# Lia_Sonic.net
KiCad netlist of a schematic drawn in EAGLE
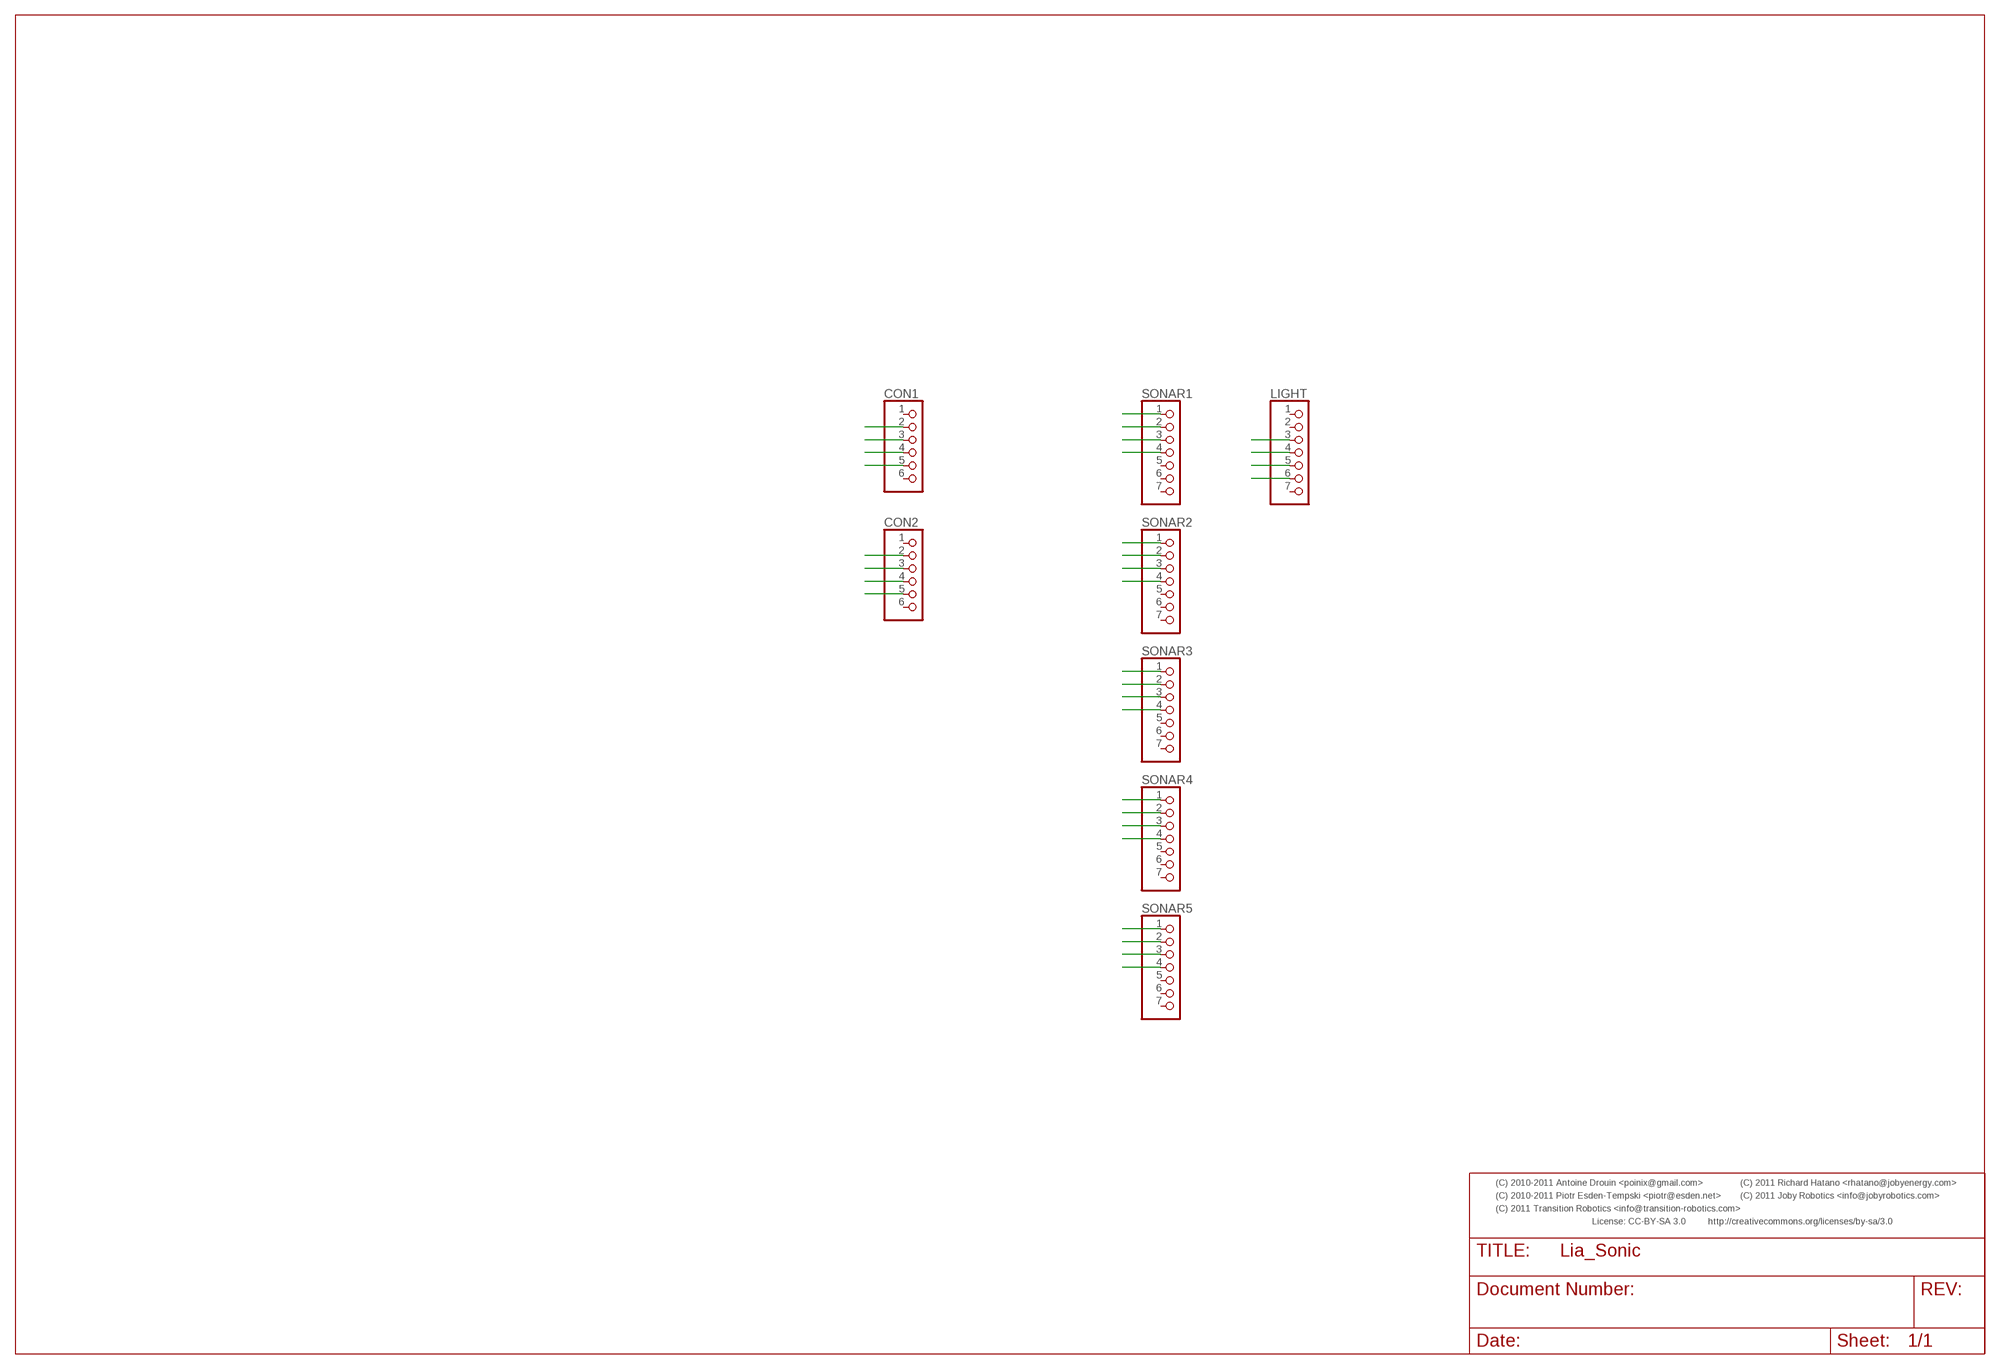
[diagram p0: schematic, sheet 1]

(export (version "E")
  (design (tool "Eeschema 10.0.6"))
  (components
    (comp (ref "CON1")
      (value "PINHD-1X6")
      (footprint "eagle-import:1X06")
      (libsource (lib "eagle-import") (part "PINHD-1X6"))
    )
    (comp (ref "CON2")
      (value "PINHD-1X6")
      (footprint "eagle-import:1X06")
      (libsource (lib "eagle-import") (part "PINHD-1X6"))
    )
    (comp (ref "LIGHT")
      (value "PINHD-1X7")
      (footprint "eagle-import:1X07")
      (libsource (lib "eagle-import") (part "PINHD-1X7"))
    )
    (comp (ref "SONAR1")
      (value "PINHD-1X7")
      (footprint "eagle-import:1X07")
      (libsource (lib "eagle-import") (part "PINHD-1X7"))
    )
    (comp (ref "SONAR2")
      (value "PINHD-1X7")
      (footprint "eagle-import:1X07")
      (libsource (lib "eagle-import") (part "PINHD-1X7"))
    )
    (comp (ref "SONAR3")
      (value "PINHD-1X7")
      (footprint "eagle-import:1X07")
      (libsource (lib "eagle-import") (part "PINHD-1X7"))
    )
    (comp (ref "SONAR4")
      (value "PINHD-1X7")
      (footprint "eagle-import:1X07")
      (libsource (lib "eagle-import") (part "PINHD-1X7"))
    )
    (comp (ref "SONAR5")
      (value "PINHD-1X7")
      (footprint "eagle-import:1X07")
      (libsource (lib "eagle-import") (part "PINHD-1X7"))
    )
  )
  (nets
    (net (code "1") (name "/GND") (class "Default")
      (node (ref "CON1") (pin "2") (pinfunction "2_2") (pintype "passive"))
      (node (ref "CON2") (pin "5") (pinfunction "5_5") (pintype "passive"))
      (node (ref "LIGHT") (pin "6") (pinfunction "6_6") (pintype "passive"))
      (node (ref "SONAR1") (pin "1") (pinfunction "1_1") (pintype "passive"))
      (node (ref "SONAR2") (pin "1") (pinfunction "1_1") (pintype "passive"))
      (node (ref "SONAR3") (pin "1") (pinfunction "1_1") (pintype "passive"))
      (node (ref "SONAR4") (pin "1") (pinfunction "1_1") (pintype "passive"))
      (node (ref "SONAR5") (pin "1") (pinfunction "1_1") (pintype "passive"))
    )
    (net (code "2") (name "/SCL") (class "Default")
      (node (ref "CON1") (pin "4") (pinfunction "4_4") (pintype "passive"))
      (node (ref "CON2") (pin "3") (pinfunction "3_3") (pintype "passive"))
      (node (ref "LIGHT") (pin "4") (pinfunction "4_4") (pintype "passive"))
      (node (ref "SONAR1") (pin "3") (pinfunction "3_3") (pintype "passive"))
      (node (ref "SONAR2") (pin "3") (pinfunction "3_3") (pintype "passive"))
      (node (ref "SONAR3") (pin "3") (pinfunction "3_3") (pintype "passive"))
      (node (ref "SONAR4") (pin "3") (pinfunction "3_3") (pintype "passive"))
      (node (ref "SONAR5") (pin "3") (pinfunction "3_3") (pintype "passive"))
    )
    (net (code "3") (name "/SDA") (class "Default")
      (node (ref "CON1") (pin "5") (pinfunction "5_5") (pintype "passive"))
      (node (ref "CON2") (pin "2") (pinfunction "2_2") (pintype "passive"))
      (node (ref "LIGHT") (pin "3") (pinfunction "3_3") (pintype "passive"))
      (node (ref "SONAR1") (pin "4") (pinfunction "4_4") (pintype "passive"))
      (node (ref "SONAR2") (pin "4") (pinfunction "4_4") (pintype "passive"))
      (node (ref "SONAR3") (pin "4") (pinfunction "4_4") (pintype "passive"))
      (node (ref "SONAR4") (pin "4") (pinfunction "4_4") (pintype "passive"))
      (node (ref "SONAR5") (pin "4") (pinfunction "4_4") (pintype "passive"))
    )
    (net (code "4") (name "/VCC") (class "Default")
      (node (ref "CON1") (pin "3") (pinfunction "3_3") (pintype "passive"))
      (node (ref "CON2") (pin "4") (pinfunction "4_4") (pintype "passive"))
      (node (ref "LIGHT") (pin "5") (pinfunction "5_5") (pintype "passive"))
      (node (ref "SONAR1") (pin "2") (pinfunction "2_2") (pintype "passive"))
      (node (ref "SONAR2") (pin "2") (pinfunction "2_2") (pintype "passive"))
      (node (ref "SONAR3") (pin "2") (pinfunction "2_2") (pintype "passive"))
      (node (ref "SONAR4") (pin "2") (pinfunction "2_2") (pintype "passive"))
      (node (ref "SONAR5") (pin "2") (pinfunction "2_2") (pintype "passive"))
    )
    (net (code "5") (name "unconnected-(CON1-Pad1)") (class "Default")
      (node (ref "CON1") (pin "1") (pinfunction "1_1") (pintype "passive"))
    )
    (net (code "6") (name "unconnected-(CON1-Pad6)") (class "Default")
      (node (ref "CON1") (pin "6") (pinfunction "6_6") (pintype "passive"))
    )
    (net (code "7") (name "unconnected-(CON2-Pad1)") (class "Default")
      (node (ref "CON2") (pin "1") (pinfunction "1_1") (pintype "passive"))
    )
    (net (code "8") (name "unconnected-(CON2-Pad6)") (class "Default")
      (node (ref "CON2") (pin "6") (pinfunction "6_6") (pintype "passive"))
    )
    (net (code "9") (name "unconnected-(LIGHT-Pad1)") (class "Default")
      (node (ref "LIGHT") (pin "1") (pinfunction "1_1") (pintype "passive"))
    )
    (net (code "10") (name "unconnected-(LIGHT-Pad2)") (class "Default")
      (node (ref "LIGHT") (pin "2") (pinfunction "2_2") (pintype "passive"))
    )
    (net (code "11") (name "unconnected-(LIGHT-Pad7)") (class "Default")
      (node (ref "LIGHT") (pin "7") (pinfunction "7_7") (pintype "passive"))
    )
    (net (code "12") (name "unconnected-(SONAR1-Pad5)") (class "Default")
      (node (ref "SONAR1") (pin "5") (pinfunction "5_5") (pintype "passive"))
    )
    (net (code "13") (name "unconnected-(SONAR1-Pad6)") (class "Default")
      (node (ref "SONAR1") (pin "6") (pinfunction "6_6") (pintype "passive"))
    )
    (net (code "14") (name "unconnected-(SONAR1-Pad7)") (class "Default")
      (node (ref "SONAR1") (pin "7") (pinfunction "7_7") (pintype "passive"))
    )
    (net (code "15") (name "unconnected-(SONAR2-Pad5)") (class "Default")
      (node (ref "SONAR2") (pin "5") (pinfunction "5_5") (pintype "passive"))
    )
    (net (code "16") (name "unconnected-(SONAR2-Pad6)") (class "Default")
      (node (ref "SONAR2") (pin "6") (pinfunction "6_6") (pintype "passive"))
    )
    (net (code "17") (name "unconnected-(SONAR2-Pad7)") (class "Default")
      (node (ref "SONAR2") (pin "7") (pinfunction "7_7") (pintype "passive"))
    )
    (net (code "18") (name "unconnected-(SONAR3-Pad5)") (class "Default")
      (node (ref "SONAR3") (pin "5") (pinfunction "5_5") (pintype "passive"))
    )
    (net (code "19") (name "unconnected-(SONAR3-Pad6)") (class "Default")
      (node (ref "SONAR3") (pin "6") (pinfunction "6_6") (pintype "passive"))
    )
    (net (code "20") (name "unconnected-(SONAR3-Pad7)") (class "Default")
      (node (ref "SONAR3") (pin "7") (pinfunction "7_7") (pintype "passive"))
    )
    (net (code "21") (name "unconnected-(SONAR4-Pad5)") (class "Default")
      (node (ref "SONAR4") (pin "5") (pinfunction "5_5") (pintype "passive"))
    )
    (net (code "22") (name "unconnected-(SONAR4-Pad6)") (class "Default")
      (node (ref "SONAR4") (pin "6") (pinfunction "6_6") (pintype "passive"))
    )
    (net (code "23") (name "unconnected-(SONAR4-Pad7)") (class "Default")
      (node (ref "SONAR4") (pin "7") (pinfunction "7_7") (pintype "passive"))
    )
    (net (code "24") (name "unconnected-(SONAR5-Pad5)") (class "Default")
      (node (ref "SONAR5") (pin "5") (pinfunction "5_5") (pintype "passive"))
    )
    (net (code "25") (name "unconnected-(SONAR5-Pad6)") (class "Default")
      (node (ref "SONAR5") (pin "6") (pinfunction "6_6") (pintype "passive"))
    )
    (net (code "26") (name "unconnected-(SONAR5-Pad7)") (class "Default")
      (node (ref "SONAR5") (pin "7") (pinfunction "7_7") (pintype "passive"))
    )
  )
)
